# SCH_AB1805_2025-06-08.net
KiCad netlist of a schematic drawn in EasyEDA
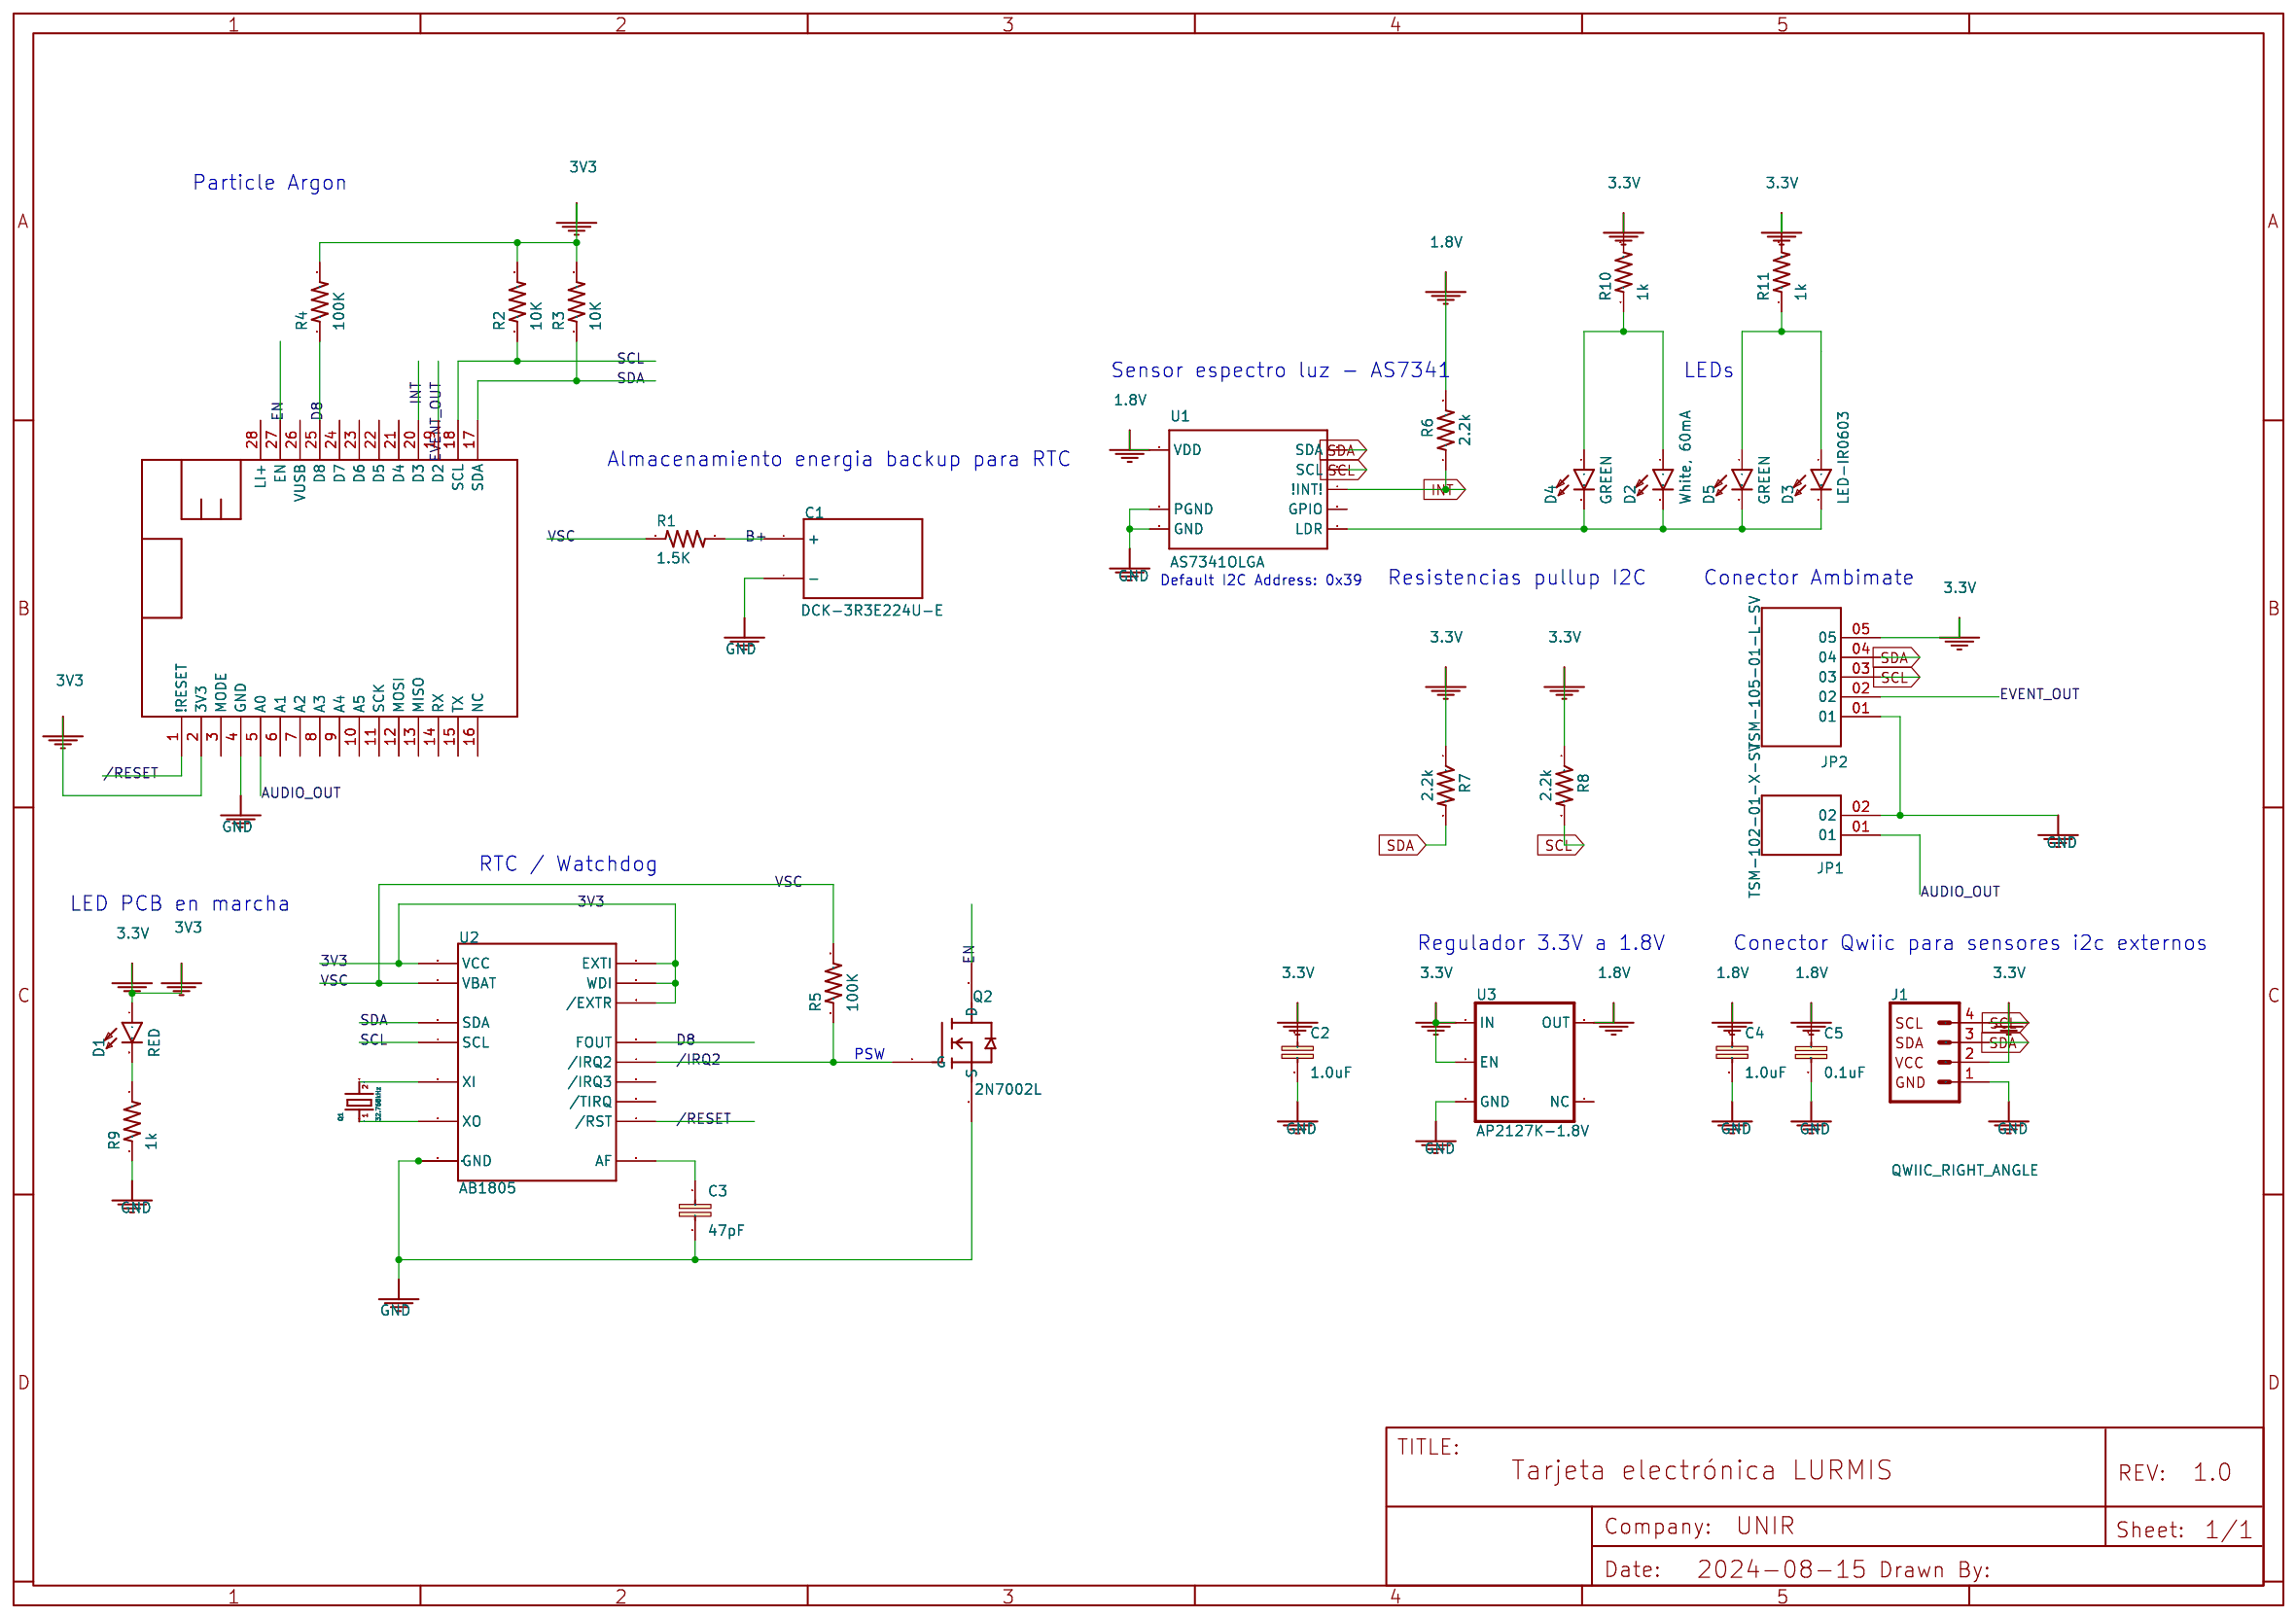
[diagram p0: schematic sheet]

(export (version "E")
  (design (tool "Eeschema 10.0.6"))
  (components
    (comp (ref "C1") (value "DCK-3R3E224U-E") (libsource (lib "") (part "Unknown_430_-530")))
    (comp (ref "C2") (value "1.0uF") (libsource (lib "") (part "Unknown_650_-275")))
    (comp (ref "C3") (value "47pF") (libsource (lib "") (part "Unknown_345_-195")))
    (comp (ref "C4") (value "1.0uF") (libsource (lib "") (part "Unknown_870_-275")))
    (comp (ref "C5") (value "0.1uF") (libsource (lib "") (part "Unknown_910_-275")))
    (comp (ref "D1") (value "RED") (libsource (lib "") (part "Unknown_60_-295")))
    (comp (ref "D2") (value "White, 60mA") (libsource (lib "") (part "Unknown_835_-575")))
    (comp (ref "D3") (value "LED-IR0603") (libsource (lib "") (part "Unknown_915_-575")))
    (comp (ref "D4") (value "GREEN") (libsource (lib "") (part "Unknown_795_-575")))
    (comp (ref "D5") (value "GREEN") (libsource (lib "") (part "Unknown_875_-575")))
    (comp (ref "J1") (value "QWIIC_RIGHT_ANGLE") (libsource (lib "") (part "Unknown_970_-275")))
    (comp (ref "JP1") (value "TSM-102-01-X-SV") (libsource (lib "") (part "Unknown_905_-390")))
    (comp (ref "JP2") (value "TSM-105-01-L-SV") (libsource (lib "") (part "Unknown_905_-470")))
    (comp (ref "MS1") (value "FEATHERWING_NODIM") (libsource (lib "") (part "Unknown_65_-450")))
    (comp (ref "Q1") (value "32.768kHz") (libsource (lib "") (part "Unknown_175_-255")))
    (comp (ref "Q2") (value "2N7002L") (libsource (lib "") (part "Unknown_475_-285")))
    (comp (ref "R1") (value "1.5K") (libsource (lib "") (part "Unknown_340_-540")))
    (comp (ref "R2") (value "10K") (libsource (lib "") (part "Unknown_255_-660")))
    (comp (ref "R3") (value "10K") (libsource (lib "") (part "Unknown_285_-660")))
    (comp (ref "R4") (value "100K") (libsource (lib "") (part "Unknown_155_-660")))
    (comp (ref "R5") (value "100K") (libsource (lib "") (part "Unknown_415_-315")))
    (comp (ref "R6") (value "2.2k") (libsource (lib "") (part "Unknown_725_-595")))
    (comp (ref "R7") (value "2.2k") (libsource (lib "") (part "Unknown_725_-415")))
    (comp (ref "R8") (value "2.2k") (libsource (lib "") (part "Unknown_785_-415")))
    (comp (ref "R9") (value "1k") (libsource (lib "") (part "Unknown_60_-245")))
    (comp (ref "R10") (value "1k") (libsource (lib "") (part "Unknown_815_-675")))
    (comp (ref "R11") (value "1k") (libsource (lib "") (part "Unknown_895_-675")))
    (comp (ref "U1") (value "AS7341OLGA") (libsource (lib "") (part "Unknown_625_-565")))
    (comp (ref "U2") (value "AB1805") (libsource (lib "") (part "Unknown_275_-305")))
    (comp (ref "U3") (value "AP2127K-1.8V") (libsource (lib "") (part "Unknown_770_-275")))
  )
  (nets
    (net (code "1") (name "/AUDIO_OUT") (class "Default")
      (node (ref "JP1") (pin "01") (pinfunction "01_01") (pintype "bidirectional"))
      (node (ref "MS1") (pin "5") (pinfunction "A0_5") (pintype "bidirectional"))
    )
    (net (code "2") (name "/B+") (class "Default")
      (node (ref "C1") (pin "+") (pinfunction "+_+") (pintype "bidirectional"))
      (node (ref "R1") (pin "2") (pinfunction "2_2") (pintype "bidirectional"))
    )
    (net (code "3") (name "/D8") (class "Default")
      (node (ref "MS1") (pin "25") (pinfunction "D8_25") (pintype "bidirectional"))
      (node (ref "R4") (pin "1") (pinfunction "1_1") (pintype "bidirectional"))
      (node (ref "U2") (pin "11") (pinfunction "FOUT_11") (pintype "bidirectional"))
    )
    (net (code "4") (name "/EN") (class "Default")
      (node (ref "MS1") (pin "27") (pinfunction "EN_27") (pintype "bidirectional"))
      (node (ref "Q2") (pin "3") (pinfunction "D_3") (pintype "bidirectional"))
    )
    (net (code "5") (name "/EVENT_OUT") (class "Default")
      (node (ref "JP2") (pin "02") (pinfunction "02_02") (pintype "bidirectional"))
      (node (ref "MS1") (pin "19") (pinfunction "D2_19") (pintype "bidirectional"))
    )
    (net (code "6") (name "/VSC") (class "Default")
      (node (ref "R1") (pin "1") (pinfunction "1_1") (pintype "bidirectional"))
      (node (ref "R5") (pin "2") (pinfunction "2_2") (pintype "bidirectional"))
      (node (ref "U2") (pin "5") (pinfunction "VBAT_5") (pintype "bidirectional"))
    )
    (net (code "7") (name "/{slash}IRQ2") (class "Default")
      (node (ref "Q2") (pin "1") (pinfunction "G_1") (pintype "bidirectional"))
      (node (ref "R5") (pin "1") (pinfunction "1_1") (pintype "bidirectional"))
      (node (ref "U2") (pin "4") (pinfunction "/IRQ2_4") (pintype "bidirectional"))
    )
    (net (code "8") (name "/{slash}RESET") (class "Default")
      (node (ref "MS1") (pin "1") (pinfunction "!RESET_1") (pintype "bidirectional"))
      (node (ref "U2") (pin "1") (pinfunction "/RST_1") (pintype "bidirectional"))
    )
    (net (code "9") (name "1.8V") (class "Default")
      (node (ref "C4") (pin "1") (pinfunction "1_1") (pintype "bidirectional"))
      (node (ref "C5") (pin "1") (pinfunction "1_1") (pintype "bidirectional"))
      (node (ref "R6") (pin "2") (pinfunction "2_2") (pintype "bidirectional"))
      (node (ref "U1") (pin "1") (pinfunction "VDD_1") (pintype "bidirectional"))
      (node (ref "U3") (pin "5") (pinfunction "OUT_5") (pintype "bidirectional"))
    )
    (net (code "10") (name "3.3V") (class "Default")
      (node (ref "C2") (pin "1") (pinfunction "1_1") (pintype "bidirectional"))
      (node (ref "D1") (pin "A") (pinfunction "A_A") (pintype "bidirectional"))
      (node (ref "J1") (pin "2") (pinfunction "2_2") (pintype "bidirectional"))
      (node (ref "JP2") (pin "05") (pinfunction "05_05") (pintype "bidirectional"))
      (node (ref "MS1") (pin "2") (pinfunction "3V3_2") (pintype "bidirectional"))
      (node (ref "R10") (pin "2") (pinfunction "2_2") (pintype "bidirectional"))
      (node (ref "R11") (pin "2") (pinfunction "2_2") (pintype "bidirectional"))
      (node (ref "R2") (pin "2") (pinfunction "2_2") (pintype "bidirectional"))
      (node (ref "R3") (pin "2") (pinfunction "2_2") (pintype "bidirectional"))
      (node (ref "R4") (pin "2") (pinfunction "2_2") (pintype "bidirectional"))
      (node (ref "R7") (pin "1") (pinfunction "1_1") (pintype "bidirectional"))
      (node (ref "R8") (pin "1") (pinfunction "1_1") (pintype "bidirectional"))
      (node (ref "U2") (pin "10") (pinfunction "EXTI_10") (pintype "bidirectional"))
      (node (ref "U2") (pin "13") (pinfunction "VCC_13") (pintype "bidirectional"))
      (node (ref "U2") (pin "2") (pinfunction "WDI_2") (pintype "bidirectional"))
      (node (ref "U2") (pin "3") (pinfunction "/EXTR_3") (pintype "bidirectional"))
      (node (ref "U3") (pin "1") (pinfunction "IN_1") (pintype "bidirectional"))
      (node (ref "U3") (pin "3") (pinfunction "EN_3") (pintype "bidirectional"))
    )
    (net (code "11") (name "GND") (class "Default")
      (node (ref "C1") (pin "-") (pinfunction "-_-") (pintype "bidirectional"))
      (node (ref "C2") (pin "2") (pinfunction "2_2") (pintype "bidirectional"))
      (node (ref "C3") (pin "2") (pinfunction "2_2") (pintype "bidirectional"))
      (node (ref "C4") (pin "2") (pinfunction "2_2") (pintype "bidirectional"))
      (node (ref "C5") (pin "2") (pinfunction "2_2") (pintype "bidirectional"))
      (node (ref "J1") (pin "1") (pinfunction "1_1") (pintype "bidirectional"))
      (node (ref "JP1") (pin "02") (pinfunction "02_02") (pintype "bidirectional"))
      (node (ref "JP2") (pin "01") (pinfunction "01_01") (pintype "bidirectional"))
      (node (ref "MS1") (pin "4") (pinfunction "GND_4") (pintype "bidirectional"))
      (node (ref "Q2") (pin "2") (pinfunction "S_2") (pintype "bidirectional"))
      (node (ref "R9") (pin "1") (pinfunction "1_1") (pintype "bidirectional"))
      (node (ref "U1") (pin "3") (pinfunction "GND_3") (pintype "bidirectional"))
      (node (ref "U1") (pin "5") (pinfunction "PGND_5") (pintype "bidirectional"))
      (node (ref "U2") (pin "9") (pinfunction "GND_9") (pintype "bidirectional"))
      (node (ref "U2") (pin "EP") (pinfunction "GND_EP") (pintype "bidirectional"))
      (node (ref "U3") (pin "2") (pinfunction "GND_2") (pintype "bidirectional"))
    )
    (net (code "12") (name "INT") (class "Default")
      (node (ref "MS1") (pin "20") (pinfunction "D3_20") (pintype "bidirectional"))
      (node (ref "R6") (pin "1") (pinfunction "1_1") (pintype "bidirectional"))
      (node (ref "U1") (pin "7") (pinfunction "!INT!_7") (pintype "bidirectional"))
    )
    (net (code "13") (name "Net-(D1-PadC)") (class "Default")
      (node (ref "D1") (pin "C") (pinfunction "C_C") (pintype "bidirectional"))
      (node (ref "R9") (pin "2") (pinfunction "2_2") (pintype "bidirectional"))
    )
    (net (code "14") (name "Net-(D2-PadA)") (class "Default")
      (node (ref "D2") (pin "A") (pinfunction "A_A") (pintype "bidirectional"))
      (node (ref "D4") (pin "A") (pinfunction "A_A") (pintype "bidirectional"))
      (node (ref "R10") (pin "1") (pinfunction "1_1") (pintype "bidirectional"))
    )
    (net (code "15") (name "Net-(D3-PadA)") (class "Default")
      (node (ref "D3") (pin "A") (pinfunction "A_A") (pintype "bidirectional"))
      (node (ref "D5") (pin "A") (pinfunction "A_A") (pintype "bidirectional"))
      (node (ref "R11") (pin "1") (pinfunction "1_1") (pintype "bidirectional"))
    )
    (net (code "16") (name "Net-(U1-LDR)") (class "Default")
      (node (ref "D2") (pin "C") (pinfunction "C_C") (pintype "bidirectional"))
      (node (ref "D3") (pin "C") (pinfunction "C_C") (pintype "bidirectional"))
      (node (ref "D4") (pin "C") (pinfunction "C_C") (pintype "bidirectional"))
      (node (ref "D5") (pin "C") (pinfunction "C_C") (pintype "bidirectional"))
      (node (ref "U1") (pin "4") (pinfunction "LDR_4") (pintype "bidirectional"))
    )
    (net (code "17") (name "Net-(U2-AF)") (class "Default")
      (node (ref "C3") (pin "1") (pinfunction "1_1") (pintype "bidirectional"))
      (node (ref "U2") (pin "14") (pinfunction "AF_14") (pintype "bidirectional"))
    )
    (net (code "18") (name "Net-(U2-XI)") (class "Default")
      (node (ref "Q1") (pin "2") (pinfunction "2_2") (pintype "bidirectional"))
      (node (ref "U2") (pin "16") (pinfunction "XI_16") (pintype "bidirectional"))
    )
    (net (code "19") (name "Net-(U2-XO)") (class "Default")
      (node (ref "Q1") (pin "1") (pinfunction "1_1") (pintype "bidirectional"))
      (node (ref "U2") (pin "15") (pinfunction "XO_15") (pintype "bidirectional"))
    )
    (net (code "20") (name "SCL") (class "Default")
      (node (ref "J1") (pin "4") (pinfunction "4_4") (pintype "bidirectional"))
      (node (ref "JP2") (pin "03") (pinfunction "03_03") (pintype "bidirectional"))
      (node (ref "MS1") (pin "18") (pinfunction "SCL_18") (pintype "bidirectional"))
      (node (ref "R2") (pin "1") (pinfunction "1_1") (pintype "bidirectional"))
      (node (ref "R8") (pin "2") (pinfunction "2_2") (pintype "bidirectional"))
      (node (ref "U1") (pin "2") (pinfunction "SCL_2") (pintype "bidirectional"))
      (node (ref "U2") (pin "7") (pinfunction "SCL_7") (pintype "bidirectional"))
    )
    (net (code "21") (name "SDA") (class "Default")
      (node (ref "J1") (pin "3") (pinfunction "3_3") (pintype "bidirectional"))
      (node (ref "JP2") (pin "04") (pinfunction "04_04") (pintype "bidirectional"))
      (node (ref "MS1") (pin "17") (pinfunction "SDA_17") (pintype "bidirectional"))
      (node (ref "R3") (pin "1") (pinfunction "1_1") (pintype "bidirectional"))
      (node (ref "R7") (pin "2") (pinfunction "2_2") (pintype "bidirectional"))
      (node (ref "U1") (pin "8") (pinfunction "SDA_8") (pintype "bidirectional"))
      (node (ref "U2") (pin "6") (pinfunction "SDA_6") (pintype "bidirectional"))
    )
    (net (code "22") (name "unconnected-(MS1-A1-Pad6)") (class "Default")
      (node (ref "MS1") (pin "6") (pinfunction "A1_6") (pintype "bidirectional"))
    )
    (net (code "23") (name "unconnected-(MS1-A2-Pad7)") (class "Default")
      (node (ref "MS1") (pin "7") (pinfunction "A2_7") (pintype "bidirectional"))
    )
    (net (code "24") (name "unconnected-(MS1-A3-Pad8)") (class "Default")
      (node (ref "MS1") (pin "8") (pinfunction "A3_8") (pintype "bidirectional"))
    )
    (net (code "25") (name "unconnected-(MS1-A4-Pad9)") (class "Default")
      (node (ref "MS1") (pin "9") (pinfunction "A4_9") (pintype "bidirectional"))
    )
    (net (code "26") (name "unconnected-(MS1-A5-Pad10)") (class "Default")
      (node (ref "MS1") (pin "10") (pinfunction "A5_10") (pintype "bidirectional"))
    )
    (net (code "27") (name "unconnected-(MS1-D4-Pad21)") (class "Default")
      (node (ref "MS1") (pin "21") (pinfunction "D4_21") (pintype "bidirectional"))
    )
    (net (code "28") (name "unconnected-(MS1-D5-Pad22)") (class "Default")
      (node (ref "MS1") (pin "22") (pinfunction "D5_22") (pintype "bidirectional"))
    )
    (net (code "29") (name "unconnected-(MS1-D6-Pad23)") (class "Default")
      (node (ref "MS1") (pin "23") (pinfunction "D6_23") (pintype "bidirectional"))
    )
    (net (code "30") (name "unconnected-(MS1-D7-Pad24)") (class "Default")
      (node (ref "MS1") (pin "24") (pinfunction "D7_24") (pintype "bidirectional"))
    )
    (net (code "31") (name "unconnected-(MS1-LI+-Pad28)") (class "Default")
      (node (ref "MS1") (pin "28") (pinfunction "LI+_28") (pintype "bidirectional"))
    )
    (net (code "32") (name "unconnected-(MS1-MISO-Pad13)") (class "Default")
      (node (ref "MS1") (pin "13") (pinfunction "MISO_13") (pintype "bidirectional"))
    )
    (net (code "33") (name "unconnected-(MS1-MODE-Pad3)") (class "Default")
      (node (ref "MS1") (pin "3") (pinfunction "MODE_3") (pintype "bidirectional"))
    )
    (net (code "34") (name "unconnected-(MS1-MOSI-Pad12)") (class "Default")
      (node (ref "MS1") (pin "12") (pinfunction "MOSI_12") (pintype "bidirectional"))
    )
    (net (code "35") (name "unconnected-(MS1-NC-Pad16)") (class "Default")
      (node (ref "MS1") (pin "16") (pinfunction "NC_16") (pintype "bidirectional"))
    )
    (net (code "36") (name "unconnected-(MS1-RX-Pad14)") (class "Default")
      (node (ref "MS1") (pin "14") (pinfunction "RX_14") (pintype "bidirectional"))
    )
    (net (code "37") (name "unconnected-(MS1-SCK-Pad11)") (class "Default")
      (node (ref "MS1") (pin "11") (pinfunction "SCK_11") (pintype "bidirectional"))
    )
    (net (code "38") (name "unconnected-(MS1-TX-Pad15)") (class "Default")
      (node (ref "MS1") (pin "15") (pinfunction "TX_15") (pintype "bidirectional"))
    )
    (net (code "39") (name "unconnected-(MS1-VUSB-Pad26)") (class "Default")
      (node (ref "MS1") (pin "26") (pinfunction "VUSB_26") (pintype "bidirectional"))
    )
    (net (code "40") (name "unconnected-(U1-GPIO-Pad6)") (class "Default")
      (node (ref "U1") (pin "6") (pinfunction "GPIO_6") (pintype "bidirectional"))
    )
    (net (code "41") (name "unconnected-(U2-{slash}IRQ3-Pad8)") (class "Default")
      (node (ref "U2") (pin "8") (pinfunction "/IRQ3_8") (pintype "bidirectional"))
    )
    (net (code "42") (name "unconnected-(U2-{slash}TIRQ-Pad12)") (class "Default")
      (node (ref "U2") (pin "12") (pinfunction "/TIRQ_12") (pintype "bidirectional"))
    )
    (net (code "43") (name "unconnected-(U3-NC-Pad4)") (class "Default")
      (node (ref "U3") (pin "4") (pinfunction "NC_4") (pintype "bidirectional"))
    )
  )
)
